# Driver_Sheet.net
KiCad netlist of a schematic drawn in Altium Designer
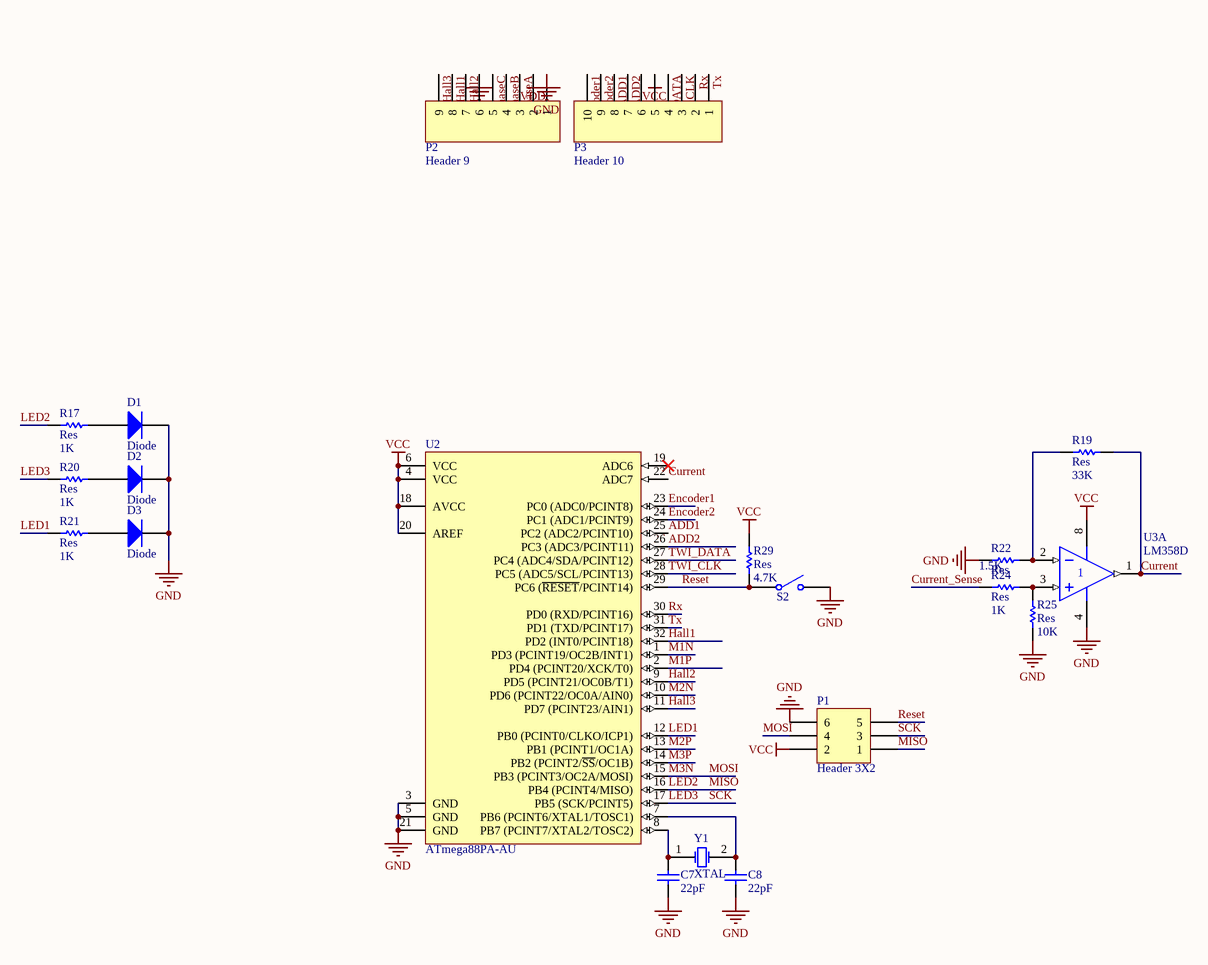
[diagram p0: Driver_Sheet.SchDoc]

(export (version "E")
  (design (tool "Eeschema 10.0.6"))
  (components
    (comp (ref "C7")
      (value "22pF")
      (footprint "2012[0805]")
      (description "Capacitor")
      (fields (field (name "Comment") "Cap_UP") (field (name "PUBLISHER") "Altium Limited"))
      (libsource (lib "KN2CLib") (part "Cap_UP"))
    )
    (comp (ref "C8")
      (value "22pF")
      (footprint "2012[0805]")
      (description "Capacitor")
      (fields (field (name "Comment") "Cap_UP") (field (name "PUBLISHER") "Altium Limited"))
      (libsource (lib "KN2CLib") (part "Cap_UP"))
    )
    (comp (ref "D1")
      (value "Diode")
      (footprint "2012[0805]")
      (description "1 Amp General Purpose Rectifier")
      (fields (field (name "PUBLISHER") "Altium Limited"))
      (libsource (lib "KN2CLib") (part "Diode"))
    )
    (comp (ref "D2")
      (value "Diode")
      (footprint "2012[0805]")
      (description "1 Amp General Purpose Rectifier")
      (fields (field (name "PUBLISHER") "Altium Limited"))
      (libsource (lib "KN2CLib") (part "Diode"))
    )
    (comp (ref "D3")
      (value "Diode")
      (footprint "2012[0805]")
      (description "1 Amp General Purpose Rectifier")
      (fields (field (name "PUBLISHER") "Altium Limited"))
      (libsource (lib "KN2CLib") (part "Diode"))
    )
    (comp (ref "P1")
      (value "Header 3X2")
      (footprint "HDRBOX2X3")
      (description "Header, 3-Pin, Dual row")
      (fields (field (name "PUBLISHER") "Altium Limited"))
      (libsource (lib "KN2CLib") (part "Header 3X2"))
    )
    (comp (ref "P2")
      (value "Header 9")
      (footprint "HDR1X9")
      (description "Header, 9-Pin")
      (fields (field (name "PUBLISHER") "Altium Limited"))
      (libsource (lib "Miscellaneous Connectors") (part "Header 9"))
    )
    (comp (ref "P3")
      (value "Header 10")
      (footprint "HDR1X10")
      (description "Header, 10-Pin")
      (fields (field (name "PUBLISHER") "Altium Limited"))
      (libsource (lib "Miscellaneous Connectors") (part "Header 10"))
    )
    (comp (ref "R17")
      (value "Res")
      (footprint "2012[0805]")
      (description "Semiconductor Resistor")
      (fields (field (name "ALTIUM_VALUE") "1K") (field (name "PUBLISHER") "Altium Limited"))
      (libsource (lib "KN2CLib") (part "Res"))
    )
    (comp (ref "R19")
      (value "Res")
      (footprint "2012[0805]")
      (description "Semiconductor Resistor")
      (fields (field (name "ALTIUM_VALUE") "33K") (field (name "PUBLISHER") "Altium Limited"))
      (libsource (lib "KN2CLib") (part "Res"))
    )
    (comp (ref "R20")
      (value "Res")
      (footprint "2012[0805]")
      (description "Semiconductor Resistor")
      (fields (field (name "ALTIUM_VALUE") "1K") (field (name "PUBLISHER") "Altium Limited"))
      (libsource (lib "KN2CLib") (part "Res"))
    )
    (comp (ref "R21")
      (value "Res")
      (footprint "2012[0805]")
      (description "Semiconductor Resistor")
      (fields (field (name "ALTIUM_VALUE") "1K") (field (name "PUBLISHER") "Altium Limited"))
      (libsource (lib "KN2CLib") (part "Res"))
    )
    (comp (ref "R22")
      (value "Res")
      (footprint "2012[0805]")
      (description "Semiconductor Resistor")
      (fields (field (name "ALTIUM_VALUE") "1.5K") (field (name "PUBLISHER") "Altium Limited"))
      (libsource (lib "KN2CLib") (part "Res"))
    )
    (comp (ref "R24")
      (value "Res")
      (footprint "2012[0805]")
      (description "Semiconductor Resistor")
      (fields (field (name "ALTIUM_VALUE") "1K") (field (name "PUBLISHER") "Altium Limited"))
      (libsource (lib "KN2CLib") (part "Res"))
    )
    (comp (ref "R25")
      (value "Res")
      (footprint "2012[0805]")
      (description "Semiconductor Resistor")
      (fields (field (name "ALTIUM_VALUE") "10K") (field (name "PUBLISHER") "Altium Limited"))
      (libsource (lib "KN2CLib") (part "Res"))
    )
    (comp (ref "R29")
      (value "Res")
      (footprint "2012[0805]")
      (description "Semiconductor Resistor")
      (fields (field (name "ALTIUM_VALUE") "4.7K") (field (name "PUBLISHER") "Altium Limited"))
      (libsource (lib "KN2CLib") (part "Res"))
    )
    (comp (ref "S2")
      (value "SW-SPST")
      (footprint "PUSH-BUT-SMD")
      (description "Single-Pole, Single-Throw Switch")
      (fields (field (name "PUBLISHER") "Altium Limited"))
      (libsource (lib "KN2CLib") (part "SW-SPST"))
    )
    (comp (ref "U2")
      (value "ATmega88PA-AU")
      (footprint "32A_N")
      (fields (field (name "PUBLISHER") "Altium Limited"))
      (libsource (lib "Atmel Microcontroller 8-Bit megaAVR") (part "ATmega88PA-AU"))
    )
    (comp (ref "U3")
      (value "LM358D")
      (footprint "751-02_N")
      (description "Dual Low-Power Operational Amplifier")
      (fields (field (name "PUBLISHER") "Altium Limited"))
      (libsource (lib "Motorola Amplifier Operational Amplifier") (part "LM358D"))
    )
    (comp (ref "Y1")
      (value "XTAL")
      (footprint "XTALL")
      (description "Crystal Oscillator")
      (fields (field (name "PUBLISHER") "Altium Limited"))
      (libsource (lib "KN2CLib") (part "XTAL"))
    )
  )
  (nets
    (net (code "1") (name "/ADD1") (class "Default")
      (node (ref "P3") (pin "8") (pinfunction "8_8") (pintype "passive"))
      (node (ref "U2") (pin "25") (pinfunction "PC2_(ADC2/PCINT10)_25") (pintype "bidirectional"))
    )
    (net (code "2") (name "/ADD2") (class "Default")
      (node (ref "P3") (pin "7") (pinfunction "7_7") (pintype "passive"))
      (node (ref "U2") (pin "26") (pinfunction "PC3_(ADC3/PCINT11)_26") (pintype "bidirectional"))
    )
    (net (code "3") (name "/Current") (class "Default")
      (node (ref "R19") (pin "1") (pinfunction "1_1") (pintype "passive"))
      (node (ref "U2") (pin "22") (pinfunction "ADC7_22") (pintype "input"))
      (node (ref "U3") (pin "1") (pinfunction "OUT_1") (pintype "output"))
    )
    (net (code "4") (name "/Current_Sense") (class "Default")
      (node (ref "R24") (pin "2") (pinfunction "2_2") (pintype "passive"))
    )
    (net (code "5") (name "/Encoder1") (class "Default")
      (node (ref "P3") (pin "10") (pinfunction "10_10") (pintype "passive"))
      (node (ref "U2") (pin "23") (pinfunction "PC0_(ADC0/PCINT8)_23") (pintype "bidirectional"))
    )
    (net (code "6") (name "/Encoder2") (class "Default")
      (node (ref "P3") (pin "9") (pinfunction "9_9") (pintype "passive"))
      (node (ref "U2") (pin "24") (pinfunction "PC1_(ADC1/PCINT9)_24") (pintype "bidirectional"))
    )
    (net (code "7") (name "/Hall1") (class "Default")
      (node (ref "P2") (pin "8") (pinfunction "8_8") (pintype "passive"))
      (node (ref "U2") (pin "32") (pinfunction "PD2_(INT0/PCINT18)_32") (pintype "bidirectional"))
    )
    (net (code "8") (name "/Hall2") (class "Default")
      (node (ref "P2") (pin "7") (pinfunction "7_7") (pintype "passive"))
      (node (ref "U2") (pin "9") (pinfunction "PD5_(PCINT21/OC0B/T1)_9") (pintype "bidirectional"))
    )
    (net (code "9") (name "/Hall3") (class "Default")
      (node (ref "P2") (pin "9") (pinfunction "9_9") (pintype "passive"))
      (node (ref "U2") (pin "11") (pinfunction "PD7_(PCINT23/AIN1)_11") (pintype "bidirectional"))
    )
    (net (code "10") (name "/LED1") (class "Default")
      (node (ref "R21") (pin "1") (pinfunction "1_1") (pintype "passive"))
      (node (ref "U2") (pin "12") (pinfunction "PB0_(PCINT0/CLKO/ICP1)_12") (pintype "bidirectional"))
    )
    (net (code "11") (name "/LED2") (class "Default")
      (node (ref "P1") (pin "1") (pinfunction "1_1") (pintype "passive"))
      (node (ref "R17") (pin "1") (pinfunction "1_1") (pintype "passive"))
      (node (ref "U2") (pin "16") (pinfunction "PB4_(PCINT4/MISO)_16") (pintype "bidirectional"))
    )
    (net (code "12") (name "/LED3") (class "Default")
      (node (ref "P1") (pin "3") (pinfunction "3_3") (pintype "passive"))
      (node (ref "R20") (pin "1") (pinfunction "1_1") (pintype "passive"))
      (node (ref "U2") (pin "17") (pinfunction "PB5_(SCK/PCINT5)_17") (pintype "bidirectional"))
    )
    (net (code "13") (name "/M1N") (class "Default")
      (node (ref "U2") (pin "1") (pinfunction "PD3_(PCINT19/OC2B/INT1)_1") (pintype "bidirectional"))
    )
    (net (code "14") (name "/M1P") (class "Default")
      (node (ref "U2") (pin "2") (pinfunction "PD4_(PCINT20/XCK/T0)_2") (pintype "bidirectional"))
    )
    (net (code "15") (name "/M2N") (class "Default")
      (node (ref "U2") (pin "10") (pinfunction "PD6_(PCINT22/OC0A/AIN0)_10") (pintype "bidirectional"))
    )
    (net (code "16") (name "/M2P") (class "Default")
      (node (ref "U2") (pin "13") (pinfunction "PB1_(PCINT1/OC1A)_13") (pintype "bidirectional"))
    )
    (net (code "17") (name "/M3N") (class "Default")
      (node (ref "P1") (pin "4") (pinfunction "4_4") (pintype "passive"))
      (node (ref "U2") (pin "15") (pinfunction "PB3_(PCINT3/OC2A/MOSI)_15") (pintype "bidirectional"))
    )
    (net (code "18") (name "/M3P") (class "Default")
      (node (ref "U2") (pin "14") (pinfunction "PB2_(PCINT2/~{SS}/OC1B)_14") (pintype "bidirectional"))
    )
    (net (code "19") (name "/PhaseA") (class "Default")
      (node (ref "P2") (pin "3") (pinfunction "3_3") (pintype "passive"))
    )
    (net (code "20") (name "/PhaseB") (class "Default")
      (node (ref "P2") (pin "4") (pinfunction "4_4") (pintype "passive"))
    )
    (net (code "21") (name "/PhaseC") (class "Default")
      (node (ref "P2") (pin "5") (pinfunction "5_5") (pintype "passive"))
    )
    (net (code "22") (name "/Reset") (class "Default")
      (node (ref "P1") (pin "5") (pinfunction "5_5") (pintype "passive"))
      (node (ref "R29") (pin "1") (pinfunction "1_1") (pintype "passive"))
      (node (ref "S2") (pin "1") (pinfunction "COMMON_1") (pintype "passive"))
      (node (ref "U2") (pin "29") (pinfunction "PC6_(~{RESET}/PCINT14)_29") (pintype "bidirectional"))
    )
    (net (code "23") (name "/Rx") (class "Default")
      (node (ref "P3") (pin "2") (pinfunction "2_2") (pintype "passive"))
      (node (ref "U2") (pin "30") (pinfunction "PD0_(RXD/PCINT16)_30") (pintype "bidirectional"))
    )
    (net (code "24") (name "/TWI_CLK") (class "Default")
      (node (ref "P3") (pin "3") (pinfunction "3_3") (pintype "passive"))
      (node (ref "U2") (pin "28") (pinfunction "PC5_(ADC5/SCL/PCINT13)_28") (pintype "bidirectional"))
    )
    (net (code "25") (name "/TWI_DATA") (class "Default")
      (node (ref "P3") (pin "4") (pinfunction "4_4") (pintype "passive"))
      (node (ref "U2") (pin "27") (pinfunction "PC4_(ADC4/SDA/PCINT12)_27") (pintype "bidirectional"))
    )
    (net (code "26") (name "/Tx") (class "Default")
      (node (ref "P3") (pin "1") (pinfunction "1_1") (pintype "passive"))
      (node (ref "U2") (pin "31") (pinfunction "PD1_(TXD/PCINT17)_31") (pintype "bidirectional"))
    )
    (net (code "27") (name "GND") (class "Default")
      (node (ref "C7") (pin "1") (pinfunction "1_1") (pintype "passive"))
      (node (ref "C8") (pin "1") (pinfunction "1_1") (pintype "passive"))
      (node (ref "D1") (pin "2") (pinfunction "K_2") (pintype "passive"))
      (node (ref "D2") (pin "2") (pinfunction "K_2") (pintype "passive"))
      (node (ref "D3") (pin "2") (pinfunction "K_2") (pintype "passive"))
      (node (ref "P1") (pin "6") (pinfunction "6_6") (pintype "passive"))
      (node (ref "P2") (pin "1") (pinfunction "1_1") (pintype "passive"))
      (node (ref "P2") (pin "6") (pinfunction "6_6") (pintype "passive"))
      (node (ref "R22") (pin "2") (pinfunction "2_2") (pintype "passive"))
      (node (ref "R25") (pin "1") (pinfunction "1_1") (pintype "passive"))
      (node (ref "S2") (pin "2") (pinfunction "NO_2") (pintype "passive"))
      (node (ref "U2") (pin "21") (pinfunction "GND_21") (pintype "power_in"))
      (node (ref "U2") (pin "3") (pinfunction "GND_3") (pintype "power_in"))
      (node (ref "U2") (pin "5") (pinfunction "GND_5") (pintype "power_in"))
      (node (ref "U3") (pin "4") (pinfunction "V-_4") (pintype "power_in"))
    )
    (net (code "28") (name "Net-(D1-A)") (class "Default")
      (node (ref "D1") (pin "1") (pinfunction "A_1") (pintype "passive"))
      (node (ref "R17") (pin "2") (pinfunction "2_2") (pintype "passive"))
    )
    (net (code "29") (name "Net-(D2-A)") (class "Default")
      (node (ref "D2") (pin "1") (pinfunction "A_1") (pintype "passive"))
      (node (ref "R20") (pin "2") (pinfunction "2_2") (pintype "passive"))
    )
    (net (code "30") (name "Net-(D3-A)") (class "Default")
      (node (ref "D3") (pin "1") (pinfunction "A_1") (pintype "passive"))
      (node (ref "R21") (pin "2") (pinfunction "2_2") (pintype "passive"))
    )
    (net (code "31") (name "Net-(U2-PB6_(PCINT6{slash}XTAL1{slash}TOSC1))") (class "Default")
      (node (ref "C8") (pin "2") (pinfunction "2_2") (pintype "passive"))
      (node (ref "U2") (pin "7") (pinfunction "PB6_(PCINT6/XTAL1/TOSC1)_7") (pintype "bidirectional"))
      (node (ref "Y1") (pin "2") (pinfunction "OSC2_2") (pintype "passive"))
    )
    (net (code "32") (name "Net-(U2-PB7_(PCINT7{slash}XTAL2{slash}TOSC2))") (class "Default")
      (node (ref "C7") (pin "2") (pinfunction "2_2") (pintype "passive"))
      (node (ref "U2") (pin "8") (pinfunction "PB7_(PCINT7/XTAL2/TOSC2)_8") (pintype "bidirectional"))
      (node (ref "Y1") (pin "1") (pinfunction "OSC1_1") (pintype "passive"))
    )
    (net (code "33") (name "Net-(U3A-IN+)") (class "Default")
      (node (ref "R24") (pin "1") (pinfunction "1_1") (pintype "passive"))
      (node (ref "R25") (pin "2") (pinfunction "2_2") (pintype "passive"))
      (node (ref "U3") (pin "3") (pinfunction "IN+_3") (pintype "input"))
    )
    (net (code "34") (name "Net-(U3A-IN-)") (class "Default")
      (node (ref "R19") (pin "2") (pinfunction "2_2") (pintype "passive"))
      (node (ref "R22") (pin "1") (pinfunction "1_1") (pintype "passive"))
      (node (ref "U3") (pin "2") (pinfunction "IN-_2") (pintype "input"))
    )
    (net (code "35") (name "VCC") (class "Default")
      (node (ref "P1") (pin "2") (pinfunction "2_2") (pintype "passive"))
      (node (ref "P3") (pin "5") (pinfunction "5_5") (pintype "passive"))
      (node (ref "R29") (pin "2") (pinfunction "2_2") (pintype "passive"))
      (node (ref "U2") (pin "18") (pinfunction "AVCC_18") (pintype "power_in"))
      (node (ref "U2") (pin "20") (pinfunction "AREF_20") (pintype "passive"))
      (node (ref "U2") (pin "4") (pinfunction "VCC_4") (pintype "power_in"))
      (node (ref "U2") (pin "6") (pinfunction "VCC_6") (pintype "power_in"))
      (node (ref "U3") (pin "8") (pinfunction "V+_8") (pintype "power_in"))
    )
    (net (code "36") (name "VDD") (class "Default")
      (node (ref "P2") (pin "2") (pinfunction "2_2") (pintype "passive"))
    )
    (net (code "37") (name "unconnected-(P3-Pad6)") (class "Default")
      (node (ref "P3") (pin "6") (pinfunction "6_6") (pintype "passive"))
    )
    (net (code "38") (name "unconnected-(U2-ADC6-Pad19)") (class "Default")
      (node (ref "U2") (pin "19") (pinfunction "ADC6_19") (pintype "input+no_connect"))
    )
  )
)
